# ft600_AD.net
KiCad netlist of a schematic drawn in Altium Designer
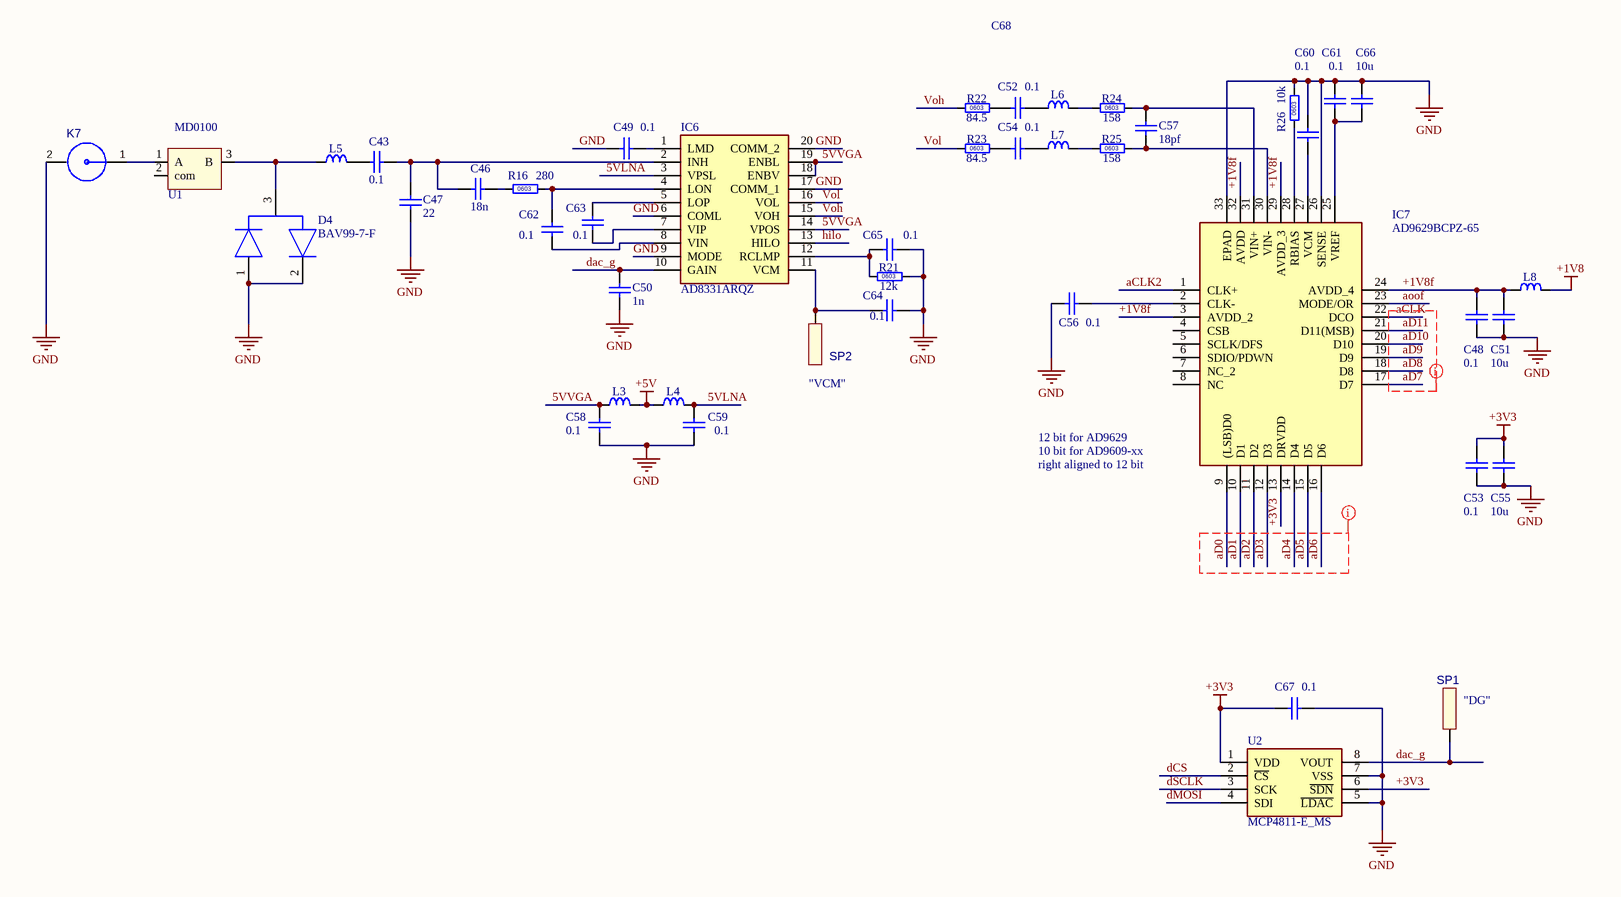
[diagram p0: ft600_AD.SchDoc]

(export (version "E")
  (design (tool "Eeschema 10.0.6"))
  (components
    (comp (ref "C43")
      (value "0.1")
      (footprint "SM0603 _3D_cap")
      (description "Capacitor  0603 inch")
      (fields (field (name "Comment") "cap0603") (field (name "PUBLISHER") "Altium Limited"))
      (libsource (lib "alt2017") (part "cap0603"))
    )
    (comp (ref "C46")
      (value "18n")
      (footprint "SM0603 _3D_cap")
      (description "Capacitor  0603 inch")
      (fields (field (name "Comment") "cap0603") (field (name "PUBLISHER") "Altium Limited"))
      (libsource (lib "alt2017") (part "cap0603"))
    )
    (comp (ref "C47")
      (value "22")
      (footprint "SM0603 _3D_cap")
      (description "Capacitor  0603 inch")
      (fields (field (name "Comment") "cap0603") (field (name "PUBLISHER") "Altium Limited"))
      (libsource (lib "alt2017") (part "cap0603"))
    )
    (comp (ref "C48")
      (value "0.1")
      (footprint "SM0603 _3D_cap")
      (description "Capacitor  0603 inch")
      (fields (field (name "Comment") "cap0603") (field (name "PUBLISHER") "Altium Limited"))
      (libsource (lib "alt2017") (part "cap0603"))
    )
    (comp (ref "C49")
      (value "0.1")
      (footprint "SM0603 _3D_cap")
      (description "Capacitor  0603 inch")
      (fields (field (name "Comment") "cap0603") (field (name "PUBLISHER") "Altium Limited"))
      (libsource (lib "alt2017") (part "cap0603"))
    )
    (comp (ref "C50")
      (value "1n")
      (footprint "SM0603 _3D_cap")
      (description "Capacitor  0603 inch")
      (fields (field (name "Comment") "cap0603") (field (name "PUBLISHER") "Altium Limited"))
      (libsource (lib "alt2017") (part "cap0603"))
    )
    (comp (ref "C51")
      (value "10u")
      (footprint "SM0603 _3D_cap")
      (description "Capacitor  0603 inch")
      (fields (field (name "Comment") "cap0603") (field (name "PUBLISHER") "Altium Limited"))
      (libsource (lib "alt2017") (part "cap0603"))
    )
    (comp (ref "C52")
      (value "0.1")
      (footprint "SM0603 _3D_cap")
      (description "Capacitor  0603 inch")
      (fields (field (name "Comment") "cap0603") (field (name "PUBLISHER") "Altium Limited"))
      (libsource (lib "alt2017") (part "cap0603"))
    )
    (comp (ref "C53")
      (value "0.1")
      (footprint "SM0603 _3D_cap")
      (description "Capacitor  0603 inch")
      (fields (field (name "Comment") "cap0603") (field (name "PUBLISHER") "Altium Limited"))
      (libsource (lib "alt2017") (part "cap0603"))
    )
    (comp (ref "C54")
      (value "0.1")
      (footprint "SM0603 _3D_cap")
      (description "Capacitor  0603 inch")
      (fields (field (name "Comment") "cap0603") (field (name "PUBLISHER") "Altium Limited"))
      (libsource (lib "alt2017") (part "cap0603"))
    )
    (comp (ref "C55")
      (value "10u")
      (footprint "SM0603 _3D_cap")
      (description "Capacitor  0603 inch")
      (fields (field (name "Comment") "cap0603") (field (name "PUBLISHER") "Altium Limited"))
      (libsource (lib "alt2017") (part "cap0603"))
    )
    (comp (ref "C56")
      (value "0.1")
      (footprint "SM0603 _3D_cap")
      (description "Capacitor  0603 inch")
      (fields (field (name "Comment") "cap0603") (field (name "PUBLISHER") "Altium Limited"))
      (libsource (lib "alt2017") (part "cap0603"))
    )
    (comp (ref "C57")
      (value "18pf")
      (footprint "SM0603 _3D_cap")
      (description "Capacitor  0603 inch")
      (fields (field (name "Comment") "cap0603") (field (name "PUBLISHER") "Altium Limited"))
      (libsource (lib "alt2017") (part "cap0603"))
    )
    (comp (ref "C58")
      (value "0.1")
      (footprint "SM0603 _3D_cap")
      (description "Capacitor  0603 inch")
      (fields (field (name "Comment") "cap0603") (field (name "PUBLISHER") "Altium Limited"))
      (libsource (lib "alt2017") (part "cap0603"))
    )
    (comp (ref "C59")
      (value "0.1")
      (footprint "SM0603 _3D_cap")
      (description "Capacitor  0603 inch")
      (fields (field (name "Comment") "cap0603") (field (name "PUBLISHER") "Altium Limited"))
      (libsource (lib "alt2017") (part "cap0603"))
    )
    (comp (ref "C60")
      (value "0.1")
      (footprint "SM0603 _3D_cap")
      (description "Capacitor  0603 inch")
      (fields (field (name "Comment") "cap0603") (field (name "PUBLISHER") "Altium Limited"))
      (libsource (lib "alt2017") (part "cap0603"))
    )
    (comp (ref "C61")
      (value "0.1")
      (footprint "SM0603 _3D_cap")
      (description "Capacitor  0603 inch")
      (fields (field (name "Comment") "cap0603") (field (name "PUBLISHER") "Altium Limited"))
      (libsource (lib "alt2017") (part "cap0603"))
    )
    (comp (ref "C62")
      (value "0.1")
      (footprint "SM0603 _3D_cap")
      (description "Capacitor  0603 inch")
      (fields (field (name "Comment") "cap0603") (field (name "PUBLISHER") "Altium Limited"))
      (libsource (lib "alt2017") (part "cap0603"))
    )
    (comp (ref "C63")
      (value "0.1")
      (footprint "SM0603 _3D_cap")
      (description "Capacitor  0603 inch")
      (fields (field (name "Comment") "cap0603") (field (name "PUBLISHER") "Altium Limited"))
      (libsource (lib "alt2017") (part "cap0603"))
    )
    (comp (ref "C64")
      (value "0.1")
      (footprint "SM0603 _3D_cap")
      (description "Capacitor  0603 inch")
      (fields (field (name "Comment") "cap0603") (field (name "PUBLISHER") "Altium Limited"))
      (libsource (lib "alt2017") (part "cap0603"))
    )
    (comp (ref "C65")
      (value "0.1")
      (footprint "SM0603 _3D_cap")
      (description "Capacitor  0603 inch")
      (fields (field (name "Comment") "cap0603") (field (name "PUBLISHER") "Altium Limited"))
      (libsource (lib "alt2017") (part "cap0603"))
    )
    (comp (ref "C66")
      (value "10u")
      (footprint "SM0603 _3D_cap")
      (description "Capacitor  0603 inch")
      (fields (field (name "Comment") "cap0603") (field (name "PUBLISHER") "Altium Limited"))
      (libsource (lib "alt2017") (part "cap0603"))
    )
    (comp (ref "C67")
      (value "0.1")
      (footprint "SM0603 _3D_cap")
      (description "Capacitor  0603 inch")
      (fields (field (name "Comment") "cap0603") (field (name "PUBLISHER") "Altium Limited"))
      (libsource (lib "alt2017") (part "cap0603"))
    )
    (comp (ref "D4")
      (value "BAV99-7-F")
      (footprint "SamacSys:SOT95P240X120-3N")
      (description "Diode")
      (fields (field (name "MOUSER PART NUMBER") "621-BAV99-F"))
      (libsource (lib "*") (part "BAV99-7-F"))
    )
    (comp (ref "IC6")
      (value "AD8331ARQZ")
      (footprint "SamacSys:SOP64P600X175-20N")
      (description "Integrated Circuit")
      (fields (field (name "MOUSER PART NUMBER") "584-AD8331ARQZ"))
      (libsource (lib "*") (part "AD8331ARQZ"))
    )
    (comp (ref "IC7")
      (value "AD9629BCPZ-65")
      (footprint "SamacSys:QFN50P500X500X100-33N")
      (description "Integrated Circuit")
      (fields (field (name "MOUSER PART NUMBER") "584-AD9629BCPZ-65"))
      (libsource (lib "*") (part "AD9629BCPZ-65"))
    )
    (comp (ref "K7")
      (value "SMA_Edge")
      (footprint "AMPHENOL_132357-11")
      (libsource (lib "alt2017") (part "SMA_Edge"))
    )
    (comp (ref "L3")
      (value "75R@100MHz")
      (footprint "SM0603_3D_res")
      (description "chip inductance 0603")
      (fields
        (field (name "PART NUMBER") "IND0805_MURATA_BLM21BB750SN1D")
        (field (name "POWER") "700mA")
        (field (name "AUTHOR") "S. Jafar")
      )
      (libsource (lib "alt_vovan") (part "chip inductance 0603"))
    )
    (comp (ref "L4")
      (value "75R@100MHz")
      (footprint "SM0603_3D_res")
      (description "chip inductance 0603")
      (fields
        (field (name "PART NUMBER") "IND0805_MURATA_BLM21BB750SN1D")
        (field (name "POWER") "700mA")
        (field (name "AUTHOR") "S. Jafar")
      )
      (libsource (lib "alt_vovan") (part "chip inductance 0603"))
    )
    (comp (ref "L5")
      (value "75R@100MHz")
      (footprint "SM0603_3D_res")
      (description "chip inductance 0603")
      (fields
        (field (name "PART NUMBER") "IND0805_MURATA_BLM21BB750SN1D")
        (field (name "POWER") "700mA")
        (field (name "AUTHOR") "S. Jafar")
      )
      (libsource (lib "alt_vovan") (part "chip inductance 0603"))
    )
    (comp (ref "L6")
      (value "75R@100MHz")
      (footprint "SM_0805_INDUCTANCE _3D")
      (description "chip inductance")
      (fields
        (field (name "PART NUMBER") "IND0805_MURATA_BLM21BB750SN1D")
        (field (name "POWER") "700mA")
        (field (name "AUTHOR") "S. Jafar")
      )
      (libsource (lib "alt_vovan") (part "Ind_Chip_0805"))
    )
    (comp (ref "L7")
      (value "75R@100MHz")
      (footprint "SM_0805_INDUCTANCE _3D")
      (description "chip inductance")
      (fields
        (field (name "PART NUMBER") "IND0805_MURATA_BLM21BB750SN1D")
        (field (name "POWER") "700mA")
        (field (name "AUTHOR") "S. Jafar")
      )
      (libsource (lib "alt_vovan") (part "Ind_Chip_0805"))
    )
    (comp (ref "L8")
      (value "75R@100MHz")
      (footprint "SM0603_3D_res")
      (description "chip inductance 0603")
      (fields
        (field (name "PART NUMBER") "IND0805_MURATA_BLM21BB750SN1D")
        (field (name "POWER") "700mA")
        (field (name "AUTHOR") "S. Jafar")
      )
      (libsource (lib "alt_vovan") (part "chip inductance 0603"))
    )
    (comp (ref "R16")
      (value "280")
      (footprint "SM0603_3D_res")
      (description "Res_0603_EU")
      (fields
        (field (name "PART NUMBER") "R1206_4K7_1%_0.25W_100PPM")
        (field (name "POWER") "0.25W")
        (field (name "AUTHOR") "CERN DEM JLC")
      )
      (libsource (lib "alt_vovan") (part "Res_0603_EU"))
    )
    (comp (ref "R21")
      (value "12k")
      (footprint "SM0603_3D_res")
      (description "Res_0603_EU")
      (fields
        (field (name "PART NUMBER") "R1206_4K7_1%_0.25W_100PPM")
        (field (name "POWER") "0.25W")
        (field (name "AUTHOR") "CERN DEM JLC")
      )
      (libsource (lib "alt_vovan") (part "Res_0603_EU"))
    )
    (comp (ref "R22")
      (value "84.5")
      (footprint "SM0603_3D_res")
      (description "Res_0603_EU")
      (fields
        (field (name "PART NUMBER") "R1206_4K7_1%_0.25W_100PPM")
        (field (name "POWER") "0.25W")
        (field (name "AUTHOR") "CERN DEM JLC")
      )
      (libsource (lib "alt_vovan") (part "Res_0603_EU"))
    )
    (comp (ref "R23")
      (value "84.5")
      (footprint "SM0603_3D_res")
      (description "Res_0603_EU")
      (fields
        (field (name "PART NUMBER") "R1206_4K7_1%_0.25W_100PPM")
        (field (name "POWER") "0.25W")
        (field (name "AUTHOR") "CERN DEM JLC")
      )
      (libsource (lib "alt_vovan") (part "Res_0603_EU"))
    )
    (comp (ref "R24")
      (value "158")
      (footprint "SM0603_3D_res")
      (description "Res_0603_EU")
      (fields
        (field (name "PART NUMBER") "R1206_4K7_1%_0.25W_100PPM")
        (field (name "POWER") "0.25W")
        (field (name "AUTHOR") "CERN DEM JLC")
      )
      (libsource (lib "alt_vovan") (part "Res_0603_EU"))
    )
    (comp (ref "R25")
      (value "158")
      (footprint "SM0603_3D_res")
      (description "Res_0603_EU")
      (fields
        (field (name "PART NUMBER") "R1206_4K7_1%_0.25W_100PPM")
        (field (name "POWER") "0.25W")
        (field (name "AUTHOR") "CERN DEM JLC")
      )
      (libsource (lib "alt_vovan") (part "Res_0603_EU"))
    )
    (comp (ref "R26")
      (value "10k")
      (footprint "SM0603_3D_res")
      (description "Res_0603_EU")
      (fields
        (field (name "PART NUMBER") "R1206_4K7_1%_0.25W_100PPM")
        (field (name "POWER") "0.25W")
        (field (name "AUTHOR") "CERN DEM JLC")
      )
      (libsource (lib "alt_vovan") (part "Res_0603_EU"))
    )
    (comp (ref "SP1")
      (value "\"DG\"")
      (footprint "SolderPad_D1mm _round")
      (description "for finger touch")
      (fields (field (name "Comment") "SolderPad D1mm_round"))
      (libsource (lib "alt2017") (part "SolderPad D1mm_round"))
    )
    (comp (ref "SP2")
      (value "\"VCM\"")
      (footprint "SolderPad_D1mm _round")
      (description "for finger touch")
      (fields (field (name "Comment") "SolderPad D1mm_round"))
      (libsource (lib "") (part "SolderPad D1mm_round_1"))
    )
    (comp (ref "U1")
      (value "T/R switch")
      (footprint "SOT89-150P409X160-3N")
      (libsource (lib "alt_vovan") (part "MD0100N8-G"))
    )
    (comp (ref "U2")
      (value "MCP4811-E_MS")
      (footprint "SamacSys:SOP65P490X110-8N")
      (description "Integrated Circuit")
      (fields
        (field (name "MANUFACTURER_PART_NUMBER") "MCP4812-E/MS")
        (field (name "MOUSER PART NUMBER") "579-MCP4812-E/MS")
      )
      (libsource (lib "alt_vovan") (part "MCP4811-E_MS"))
    )
  )
  (nets
    (net (code "1") (name "+1V8") (class "Default")
      (node (ref "L8") (pin "2") (pinfunction "2_2") (pintype "passive"))
    )
    (net (code "2") (name "+3V3") (class "Default")
      (node (ref "C53") (pin "1") (pinfunction "1_1") (pintype "passive"))
      (node (ref "C55") (pin "1") (pinfunction "1_1") (pintype "passive"))
      (node (ref "C67") (pin "2") (pinfunction "2_2") (pintype "passive"))
      (node (ref "IC7") (pin "13") (pinfunction "DRVDD_13") (pintype "passive"))
      (node (ref "U2") (pin "1") (pinfunction "VDD_1") (pintype "passive"))
      (node (ref "U2") (pin "6") (pinfunction "~{SDN}_6") (pintype "passive"))
    )
    (net (code "3") (name "+5V") (class "Default")
      (node (ref "L3") (pin "2") (pinfunction "2_2") (pintype "passive"))
      (node (ref "L4") (pin "1") (pinfunction "1_1") (pintype "passive"))
    )
    (net (code "4") (name "/+1V8f") (class "Default")
      (node (ref "C48") (pin "1") (pinfunction "1_1") (pintype "passive"))
      (node (ref "C51") (pin "1") (pinfunction "1_1") (pintype "passive"))
      (node (ref "IC7") (pin "24") (pinfunction "AVDD_4_24") (pintype "passive"))
      (node (ref "IC7") (pin "29") (pinfunction "AVDD_3_29") (pintype "passive"))
      (node (ref "IC7") (pin "3") (pinfunction "AVDD_2_3") (pintype "passive"))
      (node (ref "IC7") (pin "32") (pinfunction "AVDD_32") (pintype "passive"))
      (node (ref "L8") (pin "1") (pinfunction "1_1") (pintype "passive"))
    )
    (net (code "5") (name "/5VLNA") (class "Default")
      (node (ref "C59") (pin "2") (pinfunction "2_2") (pintype "passive"))
      (node (ref "IC6") (pin "3") (pinfunction "VPSL_3") (pintype "passive"))
      (node (ref "L4") (pin "2") (pinfunction "2_2") (pintype "passive"))
    )
    (net (code "6") (name "/5VVGA") (class "Default")
      (node (ref "C58") (pin "2") (pinfunction "2_2") (pintype "passive"))
      (node (ref "IC6") (pin "14") (pinfunction "VPOS_14") (pintype "passive"))
      (node (ref "IC6") (pin "18") (pinfunction "ENBV_18") (pintype "passive"))
      (node (ref "IC6") (pin "19") (pinfunction "ENBL_19") (pintype "passive"))
      (node (ref "L3") (pin "1") (pinfunction "1_1") (pintype "passive"))
    )
    (net (code "7") (name "/Voh") (class "Default")
      (node (ref "IC6") (pin "15") (pinfunction "VOH_15") (pintype "passive"))
      (node (ref "R22") (pin "1") (pinfunction "1_1") (pintype "passive"))
    )
    (net (code "8") (name "/Vol") (class "Default")
      (node (ref "IC6") (pin "16") (pinfunction "VOL_16") (pintype "passive"))
      (node (ref "R23") (pin "1") (pinfunction "1_1") (pintype "passive"))
    )
    (net (code "9") (name "/aCLK") (class "Default")
      (node (ref "IC7") (pin "22") (pinfunction "DCO_22") (pintype "passive"))
    )
    (net (code "10") (name "/aCLK2") (class "Default")
      (node (ref "IC7") (pin "1") (pinfunction "CLK+_1") (pintype "passive"))
    )
    (net (code "11") (name "/aD0") (class "Default")
      (node (ref "IC7") (pin "9") (pinfunction "(LSB)D0_9") (pintype "passive"))
    )
    (net (code "12") (name "/aD1") (class "Default")
      (node (ref "IC7") (pin "10") (pinfunction "D1_10") (pintype "passive"))
    )
    (net (code "13") (name "/aD2") (class "Default")
      (node (ref "IC7") (pin "11") (pinfunction "D2_11") (pintype "passive"))
    )
    (net (code "14") (name "/aD3") (class "Default")
      (node (ref "IC7") (pin "12") (pinfunction "D3_12") (pintype "passive"))
    )
    (net (code "15") (name "/aD4") (class "Default")
      (node (ref "IC7") (pin "14") (pinfunction "D4_14") (pintype "passive"))
    )
    (net (code "16") (name "/aD5") (class "Default")
      (node (ref "IC7") (pin "15") (pinfunction "D5_15") (pintype "passive"))
    )
    (net (code "17") (name "/aD6") (class "Default")
      (node (ref "IC7") (pin "16") (pinfunction "D6_16") (pintype "passive"))
    )
    (net (code "18") (name "/aD7") (class "Default")
      (node (ref "IC7") (pin "17") (pinfunction "D7_17") (pintype "passive"))
    )
    (net (code "19") (name "/aD8") (class "Default")
      (node (ref "IC7") (pin "18") (pinfunction "D8_18") (pintype "passive"))
    )
    (net (code "20") (name "/aD9") (class "Default")
      (node (ref "IC7") (pin "19") (pinfunction "D9_19") (pintype "passive"))
    )
    (net (code "21") (name "/aD10") (class "Default")
      (node (ref "IC7") (pin "20") (pinfunction "D10_20") (pintype "passive"))
    )
    (net (code "22") (name "/aD11") (class "Default")
      (node (ref "IC7") (pin "21") (pinfunction "D11(MSB)_21") (pintype "passive"))
    )
    (net (code "23") (name "/aoof") (class "Default")
      (node (ref "IC7") (pin "23") (pinfunction "MODE/OR_23") (pintype "passive"))
    )
    (net (code "24") (name "/dCS") (class "Default")
      (node (ref "U2") (pin "2") (pinfunction "~{CS}_2") (pintype "passive"))
    )
    (net (code "25") (name "/dMOSI") (class "Default")
      (node (ref "U2") (pin "4") (pinfunction "SDI_4") (pintype "passive"))
    )
    (net (code "26") (name "/dSCLK") (class "Default")
      (node (ref "U2") (pin "3") (pinfunction "SCK_3") (pintype "passive"))
    )
    (net (code "27") (name "/dac_g") (class "Default")
      (node (ref "C50") (pin "2") (pinfunction "2_2") (pintype "passive"))
      (node (ref "IC6") (pin "10") (pinfunction "GAIN_10") (pintype "passive"))
      (node (ref "SP1") (pin "1") (pinfunction "1_1") (pintype "passive"))
      (node (ref "U2") (pin "8") (pinfunction "VOUT_8") (pintype "passive"))
    )
    (net (code "28") (name "/hilo") (class "Default")
      (node (ref "IC6") (pin "13") (pinfunction "HILO_13") (pintype "passive"))
    )
    (net (code "29") (name "GND") (class "Default")
      (node (ref "C47") (pin "1") (pinfunction "1_1") (pintype "passive"))
      (node (ref "C48") (pin "2") (pinfunction "2_2") (pintype "passive"))
      (node (ref "C49") (pin "1") (pinfunction "1_1") (pintype "passive"))
      (node (ref "C50") (pin "1") (pinfunction "1_1") (pintype "passive"))
      (node (ref "C51") (pin "2") (pinfunction "2_2") (pintype "passive"))
      (node (ref "C53") (pin "2") (pinfunction "2_2") (pintype "passive"))
      (node (ref "C55") (pin "2") (pinfunction "2_2") (pintype "passive"))
      (node (ref "C56") (pin "2") (pinfunction "2_2") (pintype "passive"))
      (node (ref "C58") (pin "1") (pinfunction "1_1") (pintype "passive"))
      (node (ref "C59") (pin "1") (pinfunction "1_1") (pintype "passive"))
      (node (ref "C60") (pin "1") (pinfunction "1_1") (pintype "passive"))
      (node (ref "C61") (pin "1") (pinfunction "1_1") (pintype "passive"))
      (node (ref "C64") (pin "1") (pinfunction "1_1") (pintype "passive"))
      (node (ref "C65") (pin "1") (pinfunction "1_1") (pintype "passive"))
      (node (ref "C66") (pin "1") (pinfunction "1_1") (pintype "passive"))
      (node (ref "C67") (pin "1") (pinfunction "1_1") (pintype "passive"))
      (node (ref "D4") (pin "1") (pinfunction "ANODE_1") (pintype "passive"))
      (node (ref "D4") (pin "2") (pinfunction "CATHODE_2") (pintype "passive"))
      (node (ref "IC6") (pin "17") (pinfunction "COMM_1_17") (pintype "passive"))
      (node (ref "IC6") (pin "20") (pinfunction "COMM_2_20") (pintype "passive"))
      (node (ref "IC6") (pin "6") (pinfunction "COML_6") (pintype "passive"))
      (node (ref "IC6") (pin "9") (pinfunction "MODE_9") (pintype "passive"))
      (node (ref "IC7") (pin "26") (pinfunction "SENSE_26") (pintype "passive"))
      (node (ref "IC7") (pin "33") (pinfunction "EPAD_33") (pintype "passive"))
      (node (ref "K7") (pin "2") (pinfunction "2_2") (pintype "passive"))
      (node (ref "R21") (pin "2") (pinfunction "2_2") (pintype "passive"))
      (node (ref "R26") (pin "2") (pinfunction "2_2") (pintype "passive"))
      (node (ref "U2") (pin "5") (pinfunction "~{LDAC}_5") (pintype "passive"))
      (node (ref "U2") (pin "7") (pinfunction "VSS_7") (pintype "passive"))
    )
    (net (code "30") (name "Net-(C43-Pad1)") (class "Default")
      (node (ref "C43") (pin "1") (pinfunction "1_1") (pintype "passive"))
      (node (ref "L5") (pin "2") (pinfunction "2_2") (pintype "passive"))
    )
    (net (code "31") (name "Net-(C46-Pad1)") (class "Default")
      (node (ref "C46") (pin "1") (pinfunction "1_1") (pintype "passive"))
      (node (ref "R16") (pin "1") (pinfunction "1_1") (pintype "passive"))
    )
    (net (code "32") (name "Net-(C52-Pad1)") (class "Default")
      (node (ref "C52") (pin "1") (pinfunction "1_1") (pintype "passive"))
      (node (ref "L6") (pin "1") (pinfunction "1_1") (pintype "passive"))
    )
    (net (code "33") (name "Net-(C52-Pad2)") (class "Default")
      (node (ref "C52") (pin "2") (pinfunction "2_2") (pintype "passive"))
      (node (ref "R22") (pin "2") (pinfunction "2_2") (pintype "passive"))
    )
    (net (code "34") (name "Net-(C54-Pad1)") (class "Default")
      (node (ref "C54") (pin "1") (pinfunction "1_1") (pintype "passive"))
      (node (ref "L7") (pin "1") (pinfunction "1_1") (pintype "passive"))
    )
    (net (code "35") (name "Net-(C54-Pad2)") (class "Default")
      (node (ref "C54") (pin "2") (pinfunction "2_2") (pintype "passive"))
      (node (ref "R23") (pin "2") (pinfunction "2_2") (pintype "passive"))
    )
    (net (code "36") (name "Net-(D4-A{slash}K)") (class "Default")
      (node (ref "D4") (pin "3") (pinfunction "A/K_3") (pintype "passive"))
      (node (ref "L5") (pin "1") (pinfunction "1_1") (pintype "passive"))
      (node (ref "U1") (pin "3") (pinfunction "B_3") (pintype "passive"))
    )
    (net (code "37") (name "Net-(IC6-INH)") (class "Default")
      (node (ref "C43") (pin "2") (pinfunction "2_2") (pintype "passive"))
      (node (ref "C46") (pin "2") (pinfunction "2_2") (pintype "passive"))
      (node (ref "C47") (pin "2") (pinfunction "2_2") (pintype "passive"))
      (node (ref "IC6") (pin "2") (pinfunction "INH_2") (pintype "passive"))
    )
    (net (code "38") (name "Net-(IC6-LMD)") (class "Default")
      (node (ref "C49") (pin "2") (pinfunction "2_2") (pintype "passive"))
      (node (ref "IC6") (pin "1") (pinfunction "LMD_1") (pintype "passive"))
    )
    (net (code "39") (name "Net-(IC6-LON)") (class "Default")
      (node (ref "C62") (pin "2") (pinfunction "2_2") (pintype "passive"))
      (node (ref "IC6") (pin "4") (pinfunction "LON_4") (pintype "passive"))
      (node (ref "R16") (pin "2") (pinfunction "2_2") (pintype "passive"))
    )
    (net (code "40") (name "Net-(IC6-LOP)") (class "Default")
      (node (ref "C63") (pin "2") (pinfunction "2_2") (pintype "passive"))
      (node (ref "IC6") (pin "5") (pinfunction "LOP_5") (pintype "passive"))
    )
    (net (code "41") (name "Net-(IC6-RCLMP)") (class "Default")
      (node (ref "C65") (pin "2") (pinfunction "2_2") (pintype "passive"))
      (node (ref "IC6") (pin "12") (pinfunction "RCLMP_12") (pintype "passive"))
      (node (ref "R21") (pin "1") (pinfunction "1_1") (pintype "passive"))
    )
    (net (code "42") (name "Net-(IC6-VCM)") (class "Default")
      (node (ref "C64") (pin "2") (pinfunction "2_2") (pintype "passive"))
      (node (ref "IC6") (pin "11") (pinfunction "VCM_11") (pintype "passive"))
      (node (ref "SP2") (pin "1") (pinfunction "1_1") (pintype "passive"))
    )
    (net (code "43") (name "Net-(IC6-VIN)") (class "Default")
      (node (ref "C62") (pin "1") (pinfunction "1_1") (pintype "passive"))
      (node (ref "IC6") (pin "8") (pinfunction "VIN_8") (pintype "passive"))
    )
    (net (code "44") (name "Net-(IC6-VIP)") (class "Default")
      (node (ref "C63") (pin "1") (pinfunction "1_1") (pintype "passive"))
      (node (ref "IC6") (pin "7") (pinfunction "VIP_7") (pintype "passive"))
    )
    (net (code "45") (name "Net-(IC7-CLK-)") (class "Default")
      (node (ref "C56") (pin "1") (pinfunction "1_1") (pintype "passive"))
      (node (ref "IC7") (pin "2") (pinfunction "CLK-_2") (pintype "passive"))
    )
    (net (code "46") (name "Net-(IC7-RBIAS)") (class "Default")
      (node (ref "IC7") (pin "28") (pinfunction "RBIAS_28") (pintype "passive"))
      (node (ref "R26") (pin "1") (pinfunction "1_1") (pintype "passive"))
    )
    (net (code "47") (name "Net-(IC7-VCM)") (class "Default")
      (node (ref "C60") (pin "2") (pinfunction "2_2") (pintype "passive"))
      (node (ref "IC7") (pin "27") (pinfunction "VCM_27") (pintype "passive"))
    )
    (net (code "48") (name "Net-(IC7-VIN+)") (class "Default")
      (node (ref "C57") (pin "1") (pinfunction "1_1") (pintype "passive"))
      (node (ref "IC7") (pin "31") (pinfunction "VIN+_31") (pintype "passive"))
      (node (ref "R24") (pin "2") (pinfunction "2_2") (pintype "passive"))
    )
    (net (code "49") (name "Net-(IC7-VIN-)") (class "Default")
      (node (ref "C57") (pin "2") (pinfunction "2_2") (pintype "passive"))
      (node (ref "IC7") (pin "30") (pinfunction "VIN-_30") (pintype "passive"))
      (node (ref "R25") (pin "2") (pinfunction "2_2") (pintype "passive"))
    )
    (net (code "50") (name "Net-(IC7-VREF)") (class "Default")
      (node (ref "C61") (pin "2") (pinfunction "2_2") (pintype "passive"))
      (node (ref "C66") (pin "2") (pinfunction "2_2") (pintype "passive"))
      (node (ref "IC7") (pin "25") (pinfunction "VREF_25") (pintype "passive"))
    )
    (net (code "51") (name "Net-(L6-Pad2)") (class "Default")
      (node (ref "L6") (pin "2") (pinfunction "2_2") (pintype "passive"))
      (node (ref "R24") (pin "1") (pinfunction "1_1") (pintype "passive"))
    )
    (net (code "52") (name "Net-(L7-Pad2)") (class "Default")
      (node (ref "L7") (pin "2") (pinfunction "2_2") (pintype "passive"))
      (node (ref "R25") (pin "1") (pinfunction "1_1") (pintype "passive"))
    )
    (net (code "53") (name "Net-(U1-A)") (class "Default")
      (node (ref "K7") (pin "1") (pinfunction "1_1") (pintype "passive"))
      (node (ref "U1") (pin "1") (pinfunction "A_1") (pintype "passive"))
    )
    (net (code "54") (name "unconnected-(IC7-CSB-Pad4)") (class "Default")
      (node (ref "IC7") (pin "4") (pinfunction "CSB_4") (pintype "passive"))
    )
    (net (code "55") (name "unconnected-(IC7-NC-Pad8)") (class "Default")
      (node (ref "IC7") (pin "8") (pinfunction "NC_8") (pintype "passive"))
    )
    (net (code "56") (name "unconnected-(IC7-NC_2-Pad7)") (class "Default")
      (node (ref "IC7") (pin "7") (pinfunction "NC_2_7") (pintype "passive"))
    )
    (net (code "57") (name "unconnected-(IC7-SCLK{slash}DFS-Pad5)") (class "Default")
      (node (ref "IC7") (pin "5") (pinfunction "SCLK/DFS_5") (pintype "passive"))
    )
    (net (code "58") (name "unconnected-(IC7-SDIO{slash}PDWN-Pad6)") (class "Default")
      (node (ref "IC7") (pin "6") (pinfunction "SDIO/PDWN_6") (pintype "passive"))
    )
    (net (code "59") (name "unconnected-(U1-com-Pad2)") (class "Default")
      (node (ref "U1") (pin "2") (pinfunction "com_2") (pintype "passive"))
    )
  )
)
